# leoTracker.net
KiCad netlist of a schematic drawn in EAGLE
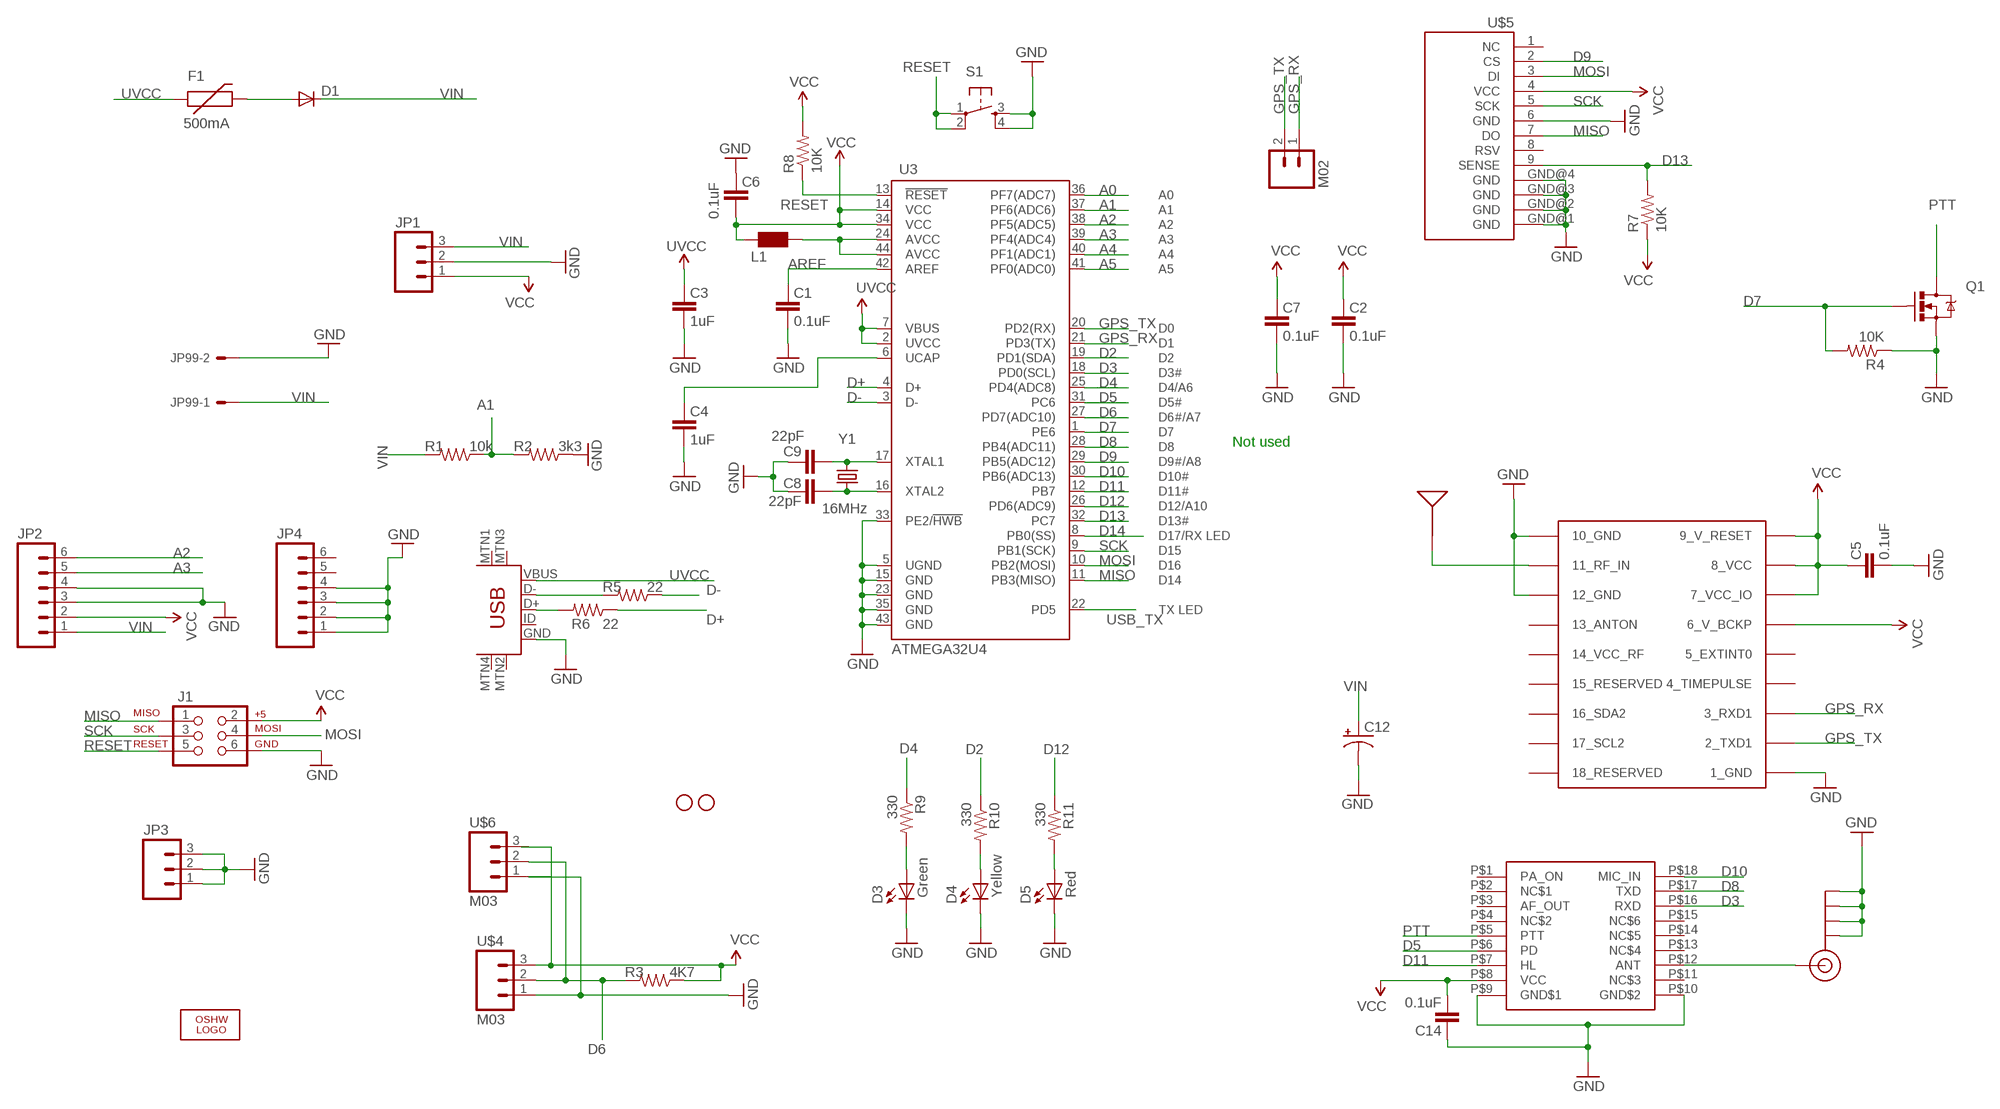
[diagram p0: schematic, sheet 1]

(export (version "E")
  (design (tool "Eeschema 10.0.6"))
  (components
    (comp (ref "C1")
      (value "0.1uF")
      (footprint "eagle-import:0805")
      (libsource (lib "eagle-import") (part "SparkFun-Capacitors_CAP0805"))
    )
    (comp (ref "C2")
      (value "0.1uF")
      (footprint "eagle-import:0402-CAP")
      (libsource (lib "eagle-import") (part "CAP0402-CAP"))
    )
    (comp (ref "C3")
      (value "1uF")
      (footprint "eagle-import:0805")
      (libsource (lib "eagle-import") (part "SparkFun-Capacitors_CAP0805"))
    )
    (comp (ref "C4")
      (value "1uF")
      (footprint "eagle-import:0805")
      (libsource (lib "eagle-import") (part "SparkFun-Capacitors_CAP0805"))
    )
    (comp (ref "C5")
      (value "0.1uF")
      (footprint "eagle-import:0805")
      (libsource (lib "eagle-import") (part "SparkFun-Capacitors_CAP0805"))
    )
    (comp (ref "C6")
      (value "0.1uF")
      (footprint "eagle-import:0805")
      (libsource (lib "eagle-import") (part "SparkFun-Capacitors_CAP0805"))
    )
    (comp (ref "C7")
      (value "0.1uF")
      (footprint "eagle-import:0402-CAP")
      (libsource (lib "eagle-import") (part "CAP0402-CAP"))
    )
    (comp (ref "C8")
      (value "22pF")
      (footprint "eagle-import:0805")
      (libsource (lib "eagle-import") (part "SparkFun-Capacitors_CAP0805"))
    )
    (comp (ref "C9")
      (value "22pF")
      (footprint "eagle-import:0805")
      (libsource (lib "eagle-import") (part "SparkFun-Capacitors_CAP0805"))
    )
    (comp (ref "C12")
      (value "CPOL-US153CLV-0405")
      (footprint "eagle-import:153CLV-0405")
      (libsource (lib "eagle-import") (part "CPOL-US153CLV-0405"))
    )
    (comp (ref "C14")
      (value "0.1uF")
      (footprint "eagle-import:0805")
      (libsource (lib "eagle-import") (part "SparkFun-Capacitors_CAP0805"))
    )
    (comp (ref "D1")
      (value "DIODESOD")
      (footprint "eagle-import:SOD-323")
      (libsource (lib "eagle-import") (part "DIODESOD"))
    )
    (comp (ref "D3")
      (value "Green")
      (footprint "eagle-import:LED-0603")
      (libsource (lib "eagle-import") (part "LED0603"))
    )
    (comp (ref "D4")
      (value "Yellow")
      (footprint "eagle-import:LED-0603")
      (libsource (lib "eagle-import") (part "LED0603"))
    )
    (comp (ref "D5")
      (value "Red")
      (footprint "eagle-import:LED-0603")
      (libsource (lib "eagle-import") (part "LED0603"))
    )
    (comp (ref "F1")
      (value "500mA")
      (footprint "eagle-import:PTC-1206")
      (libsource (lib "eagle-import") (part "PTCSMD"))
    )
    (comp (ref "J$1")
      (value "SMA_EDGE")
      (footprint "eagle-import:SMA-EDGE")
      (libsource (lib "eagle-import") (part "SMA_EDGE"))
    )
    (comp (ref "J1")
      (value "AVR_SPI_PRG_6PTH")
      (footprint "eagle-import:2X3")
      (libsource (lib "eagle-import") (part "AVR_SPI_PRG_6PTH"))
    )
    (comp (ref "JP1")
      (value "M03LOCK")
      (footprint "eagle-import:1X03_LOCK")
      (libsource (lib "eagle-import") (part "M03LOCK"))
    )
    (comp (ref "JP2")
      (value "M06LOCK")
      (footprint "eagle-import:1X06_LOCK")
      (libsource (lib "eagle-import") (part "M06LOCK"))
    )
    (comp (ref "JP3")
      (value "M03LOCK")
      (footprint "eagle-import:1X03_LOCK")
      (libsource (lib "eagle-import") (part "M03LOCK"))
    )
    (comp (ref "JP4")
      (value "M06LOCK")
      (footprint "eagle-import:1X06_LOCK")
      (libsource (lib "eagle-import") (part "M06LOCK"))
    )
    (comp (ref "JP99")
      (value "22-27-2021-02")
      (footprint "eagle-import:6410-02")
      (libsource (lib "eagle-import") (part "22-?-0227-2021"))
    )
    (comp (ref "L1")
      (value "MH2029-300Y")
      (footprint "eagle-import:0805")
      (libsource (lib "eagle-import") (part "WE-CBF_0805"))
    )
    (comp (ref "LOGO1")
      (value "OSHW_LOGO_8MILX0200-NT")
      (footprint "eagle-import:OSHW_8X200_NOTEXT")
      (libsource (lib "eagle-import") (part "OSHW_LOGO_8MILX0200-NT"))
    )
    (comp (ref "Q1")
      (value "MOSFET-NCHANNELSMD")
      (footprint "eagle-import:SOT23-3")
      (libsource (lib "eagle-import") (part "MOSFET-NCHANNELSMD"))
    )
    (comp (ref "R1")
      (value "10k")
      (footprint "eagle-import:0805")
      (libsource (lib "eagle-import") (part "RESISTOR0805-RES"))
    )
    (comp (ref "R2")
      (value "3k3")
      (footprint "eagle-import:0805")
      (libsource (lib "eagle-import") (part "RESISTOR0805-RES"))
    )
    (comp (ref "R3")
      (value "4K7")
      (footprint "eagle-import:0805")
      (libsource (lib "eagle-import") (part "RESISTOR0805-RES"))
    )
    (comp (ref "R4")
      (value "10K")
      (footprint "eagle-import:0805")
      (libsource (lib "eagle-import") (part "RESISTOR0805-RES"))
    )
    (comp (ref "R5")
      (value "22")
      (footprint "eagle-import:0805")
      (libsource (lib "eagle-import") (part "RESISTOR0805-RES"))
    )
    (comp (ref "R6")
      (value "22")
      (footprint "eagle-import:0805")
      (libsource (lib "eagle-import") (part "RESISTOR0805-RES"))
    )
    (comp (ref "R7")
      (value "10K")
      (footprint "eagle-import:0805")
      (libsource (lib "eagle-import") (part "RESISTOR0805-RES"))
    )
    (comp (ref "R8")
      (value "10K")
      (footprint "eagle-import:0805")
      (libsource (lib "eagle-import") (part "RESISTOR0805-RES"))
    )
    (comp (ref "R9")
      (value "330")
      (footprint "eagle-import:0805")
      (libsource (lib "eagle-import") (part "RESISTOR0805-RES"))
    )
    (comp (ref "R10")
      (value "330")
      (footprint "eagle-import:0805")
      (libsource (lib "eagle-import") (part "RESISTOR0805-RES"))
    )
    (comp (ref "R11")
      (value "330")
      (footprint "eagle-import:0805")
      (libsource (lib "eagle-import") (part "RESISTOR0805-RES"))
    )
    (comp (ref "S1")
      (value "TAC_SWITCHSMD")
      (footprint "eagle-import:TACTILE_SWITCH_SMD")
      (libsource (lib "eagle-import") (part "TAC_SWITCHSMD"))
    )
    (comp (ref "STANDOFF1")
      (value "STAND-OFFTIGHT")
      (footprint "eagle-import:STAND-OFF-TIGHT")
      (libsource (lib "eagle-import") (part "STAND-OFFTIGHT"))
    )
    (comp (ref "STANDOFF2")
      (value "STAND-OFFTIGHT")
      (footprint "eagle-import:STAND-OFF-TIGHT")
      (libsource (lib "eagle-import") (part "STAND-OFFTIGHT"))
    )
    (comp (ref "U$1")
      (value "ANTENNA2SMD6")
      (footprint "eagle-import:ANTENNA-CHIP6")
      (libsource (lib "eagle-import") (part "ANTENNA2SMD6"))
    )
    (comp (ref "U$2")
      (value "UBLOX_MAX")
      (footprint "eagle-import:UBLOX_MAX")
      (libsource (lib "eagle-import") (part "UBLOX_MAX"))
    )
    (comp (ref "U$4")
      (value "M03")
      (footprint "eagle-import:M03-JST")
      (libsource (lib "eagle-import") (part "M03"))
    )
    (comp (ref "U$5")
      (value "MICROSD_PI")
      (footprint "eagle-import:MICROSD_PP")
      (libsource (lib "eagle-import") (part "MICROSD_PI"))
    )
    (comp (ref "U$6")
      (value "M03")
      (footprint "eagle-import:M03-JST")
      (libsource (lib "eagle-import") (part "M03"))
    )
    (comp (ref "U$7")
      (value "SA818")
      (footprint "eagle-import:SA818")
      (libsource (lib "eagle-import") (part "SA818"))
    )
    (comp (ref "U$8")
      (value "M02")
      (footprint "eagle-import:M02")
      (libsource (lib "eagle-import") (part "M02"))
    )
    (comp (ref "U3")
      (value "ATMEGA32U4")
      (footprint "eagle-import:SPARKFUN-DIGITALIC_TQFP44")
      (libsource (lib "eagle-import") (part "ATMEGA32U4TQFP"))
    )
    (comp (ref "X1")
      (value "USB-MINIB-5PIN")
      (footprint "eagle-import:USB-MINIB")
      (libsource (lib "eagle-import") (part "USB-MINIB-5PIN"))
    )
    (comp (ref "Y1")
      (value "16MHz")
      (footprint "eagle-import:ABRACON_ABM3_CRYSTAL")
      (libsource (lib "eagle-import") (part "ABRACON_ABM3_CRYSTAL"))
    )
  )
  (nets
    (net (code "1") (name "/A0") (class "Default")
      (node (ref "U3") (pin "36") (pinfunction "PF7(ADC7)_36") (pintype "bidirectional"))
    )
    (net (code "2") (name "/A1") (class "Default")
      (node (ref "R1") (pin "1") (pinfunction "1_1") (pintype "passive"))
      (node (ref "R2") (pin "2") (pinfunction "2_2") (pintype "passive"))
      (node (ref "U3") (pin "37") (pinfunction "PF6(ADC6)_37") (pintype "bidirectional"))
    )
    (net (code "3") (name "/A2") (class "Default")
      (node (ref "JP2") (pin "6") (pinfunction "6_6") (pintype "passive"))
      (node (ref "U3") (pin "38") (pinfunction "PF5(ADC5)_38") (pintype "bidirectional"))
    )
    (net (code "4") (name "/A3") (class "Default")
      (node (ref "JP2") (pin "5") (pinfunction "5_5") (pintype "passive"))
      (node (ref "U3") (pin "39") (pinfunction "PF4(ADC4)_39") (pintype "bidirectional"))
    )
    (net (code "5") (name "/A4") (class "Default")
      (node (ref "U3") (pin "40") (pinfunction "PF1(ADC1)_40") (pintype "bidirectional"))
    )
    (net (code "6") (name "/A5") (class "Default")
      (node (ref "U3") (pin "41") (pinfunction "PF0(ADC0)_41") (pintype "bidirectional"))
    )
    (net (code "7") (name "/AREF") (class "Default")
      (node (ref "C1") (pin "2") (pinfunction "2_2") (pintype "passive"))
      (node (ref "U3") (pin "42") (pinfunction "AREF_42") (pintype "bidirectional"))
    )
    (net (code "8") (name "/D+") (class "Default")
      (node (ref "R6") (pin "1") (pinfunction "1_1") (pintype "passive"))
      (node (ref "U3") (pin "4") (pinfunction "D+_4") (pintype "bidirectional"))
    )
    (net (code "9") (name "/D-") (class "Default")
      (node (ref "R5") (pin "1") (pinfunction "1_1") (pintype "passive"))
      (node (ref "U3") (pin "3") (pinfunction "D-_3") (pintype "bidirectional"))
    )
    (net (code "10") (name "/D2") (class "Default")
      (node (ref "R10") (pin "1") (pinfunction "1_1") (pintype "passive"))
      (node (ref "U3") (pin "19") (pinfunction "PD1(SDA)_19") (pintype "bidirectional"))
    )
    (net (code "11") (name "/D3") (class "Default")
      (node (ref "U$7") (pin "P$16") (pinfunction "RXD_P$16") (pintype "bidirectional"))
      (node (ref "U3") (pin "18") (pinfunction "PD0(SCL)_18") (pintype "bidirectional"))
    )
    (net (code "12") (name "/D4") (class "Default")
      (node (ref "R9") (pin "1") (pinfunction "1_1") (pintype "passive"))
      (node (ref "U3") (pin "25") (pinfunction "PD4(ADC8)_25") (pintype "bidirectional"))
    )
    (net (code "13") (name "/D5") (class "Default")
      (node (ref "U$7") (pin "P$6") (pinfunction "PD_P$6") (pintype "bidirectional"))
      (node (ref "U3") (pin "31") (pinfunction "PC6_31") (pintype "bidirectional"))
    )
    (net (code "14") (name "/D6") (class "Default")
      (node (ref "R3") (pin "2") (pinfunction "2_2") (pintype "passive"))
      (node (ref "U$4") (pin "2") (pinfunction "2_2") (pintype "passive"))
      (node (ref "U$6") (pin "2") (pinfunction "2_2") (pintype "passive"))
      (node (ref "U3") (pin "27") (pinfunction "PD7(ADC10)_27") (pintype "bidirectional"))
    )
    (net (code "15") (name "/D7") (class "Default")
      (node (ref "Q1") (pin "1") (pinfunction "G_1") (pintype "passive"))
      (node (ref "R4") (pin "2") (pinfunction "2_2") (pintype "passive"))
      (node (ref "U3") (pin "1") (pinfunction "PE6_1") (pintype "bidirectional"))
    )
    (net (code "16") (name "/D8") (class "Default")
      (node (ref "U$7") (pin "P$17") (pinfunction "TXD_P$17") (pintype "bidirectional"))
      (node (ref "U3") (pin "28") (pinfunction "PB4(ADC11)_28") (pintype "bidirectional"))
    )
    (net (code "17") (name "/D9") (class "Default")
      (node (ref "U$5") (pin "2") (pinfunction "CS_2") (pintype "bidirectional"))
      (node (ref "U3") (pin "29") (pinfunction "PB5(ADC12)_29") (pintype "bidirectional"))
    )
    (net (code "18") (name "/D10") (class "Default")
      (node (ref "U$7") (pin "P$18") (pinfunction "MIC_IN_P$18") (pintype "bidirectional"))
      (node (ref "U3") (pin "30") (pinfunction "PB6(ADC13)_30") (pintype "bidirectional"))
    )
    (net (code "19") (name "/D11") (class "Default")
      (node (ref "U$7") (pin "P$7") (pinfunction "HL_P$7") (pintype "bidirectional"))
      (node (ref "U3") (pin "12") (pinfunction "PB7_12") (pintype "bidirectional"))
    )
    (net (code "20") (name "/D12") (class "Default")
      (node (ref "R11") (pin "1") (pinfunction "1_1") (pintype "passive"))
      (node (ref "U3") (pin "26") (pinfunction "PD6(ADC9)_26") (pintype "bidirectional"))
    )
    (net (code "21") (name "/D13") (class "Default")
      (node (ref "R7") (pin "2") (pinfunction "2_2") (pintype "passive"))
      (node (ref "U$5") (pin "9") (pinfunction "SENSE_9") (pintype "bidirectional"))
      (node (ref "U3") (pin "32") (pinfunction "PC7_32") (pintype "bidirectional"))
    )
    (net (code "22") (name "/D14") (class "Default")
      (node (ref "U3") (pin "8") (pinfunction "PB0(SS)_8") (pintype "bidirectional"))
    )
    (net (code "23") (name "/GPS_RX") (class "Default")
      (node (ref "U$2") (pin "3_RXD1") (pinfunction "3_RXD1_3_RXD1") (pintype "bidirectional"))
      (node (ref "U$8") (pin "1") (pinfunction "1_1") (pintype "passive"))
      (node (ref "U3") (pin "21") (pinfunction "PD3(TX)_21") (pintype "bidirectional"))
    )
    (net (code "24") (name "/GPS_TX") (class "Default")
      (node (ref "U$2") (pin "2_TXD1") (pinfunction "2_TXD1_2_TXD1") (pintype "bidirectional"))
      (node (ref "U$8") (pin "2") (pinfunction "2_2") (pintype "passive"))
      (node (ref "U3") (pin "20") (pinfunction "PD2(RX)_20") (pintype "bidirectional"))
    )
    (net (code "25") (name "/MISO") (class "Default")
      (node (ref "J1") (pin "1") (pinfunction "1_1") (pintype "passive"))
      (node (ref "U$5") (pin "7") (pinfunction "DO_7") (pintype "bidirectional"))
      (node (ref "U3") (pin "11") (pinfunction "PB3(MISO)_11") (pintype "bidirectional"))
    )
    (net (code "26") (name "/MOSI") (class "Default")
      (node (ref "J1") (pin "4") (pinfunction "4_4") (pintype "passive"))
      (node (ref "U$5") (pin "3") (pinfunction "DI_3") (pintype "bidirectional"))
      (node (ref "U3") (pin "10") (pinfunction "PB2(MOSI)_10") (pintype "bidirectional"))
    )
    (net (code "27") (name "/PTT") (class "Default")
      (node (ref "Q1") (pin "3") (pinfunction "D_3") (pintype "passive"))
      (node (ref "U$7") (pin "P$5") (pinfunction "PTT_P$5") (pintype "bidirectional"))
    )
    (net (code "28") (name "/RESET") (class "Default")
      (node (ref "J1") (pin "5") (pinfunction "5_5") (pintype "passive"))
      (node (ref "R8") (pin "1") (pinfunction "1_1") (pintype "passive"))
      (node (ref "S1") (pin "1") (pinfunction "1_1") (pintype "passive"))
      (node (ref "S1") (pin "2") (pinfunction "2_2") (pintype "passive"))
      (node (ref "U3") (pin "13") (pinfunction "~{RESET}_13") (pintype "bidirectional"))
    )
    (net (code "29") (name "/SCK") (class "Default")
      (node (ref "J1") (pin "3") (pinfunction "3_3") (pintype "passive"))
      (node (ref "U$5") (pin "5") (pinfunction "SCK_5") (pintype "bidirectional"))
      (node (ref "U3") (pin "9") (pinfunction "PB1(SCK)_9") (pintype "bidirectional"))
    )
    (net (code "30") (name "/USB_TX") (class "Default")
      (node (ref "U3") (pin "22") (pinfunction "PD5_22") (pintype "bidirectional"))
    )
    (net (code "31") (name "/VIN") (class "Default")
      (node (ref "C12") (pin "+") (pinfunction "+_+") (pintype "passive"))
      (node (ref "D1") (pin "1") (pinfunction "C_1") (pintype "passive"))
      (node (ref "JP1") (pin "3") (pinfunction "3_3") (pintype "passive"))
      (node (ref "JP2") (pin "1") (pinfunction "1_1") (pintype "passive"))
      (node (ref "JP99") (pin "1") (pinfunction "S_1") (pintype "passive"))
      (node (ref "R1") (pin "2") (pinfunction "2_2") (pintype "passive"))
    )
    (net (code "32") (name "GND") (class "Default")
      (node (ref "C1") (pin "1") (pinfunction "1_1") (pintype "passive"))
      (node (ref "C12") (pin "-") (pinfunction "-_-") (pintype "passive"))
      (node (ref "C14") (pin "2") (pinfunction "2_2") (pintype "passive"))
      (node (ref "C2") (pin "1") (pinfunction "1_1") (pintype "passive"))
      (node (ref "C3") (pin "1") (pinfunction "1_1") (pintype "passive"))
      (node (ref "C4") (pin "1") (pinfunction "1_1") (pintype "passive"))
      (node (ref "C5") (pin "1") (pinfunction "1_1") (pintype "passive"))
      (node (ref "C6") (pin "2") (pinfunction "2_2") (pintype "passive"))
      (node (ref "C7") (pin "1") (pinfunction "1_1") (pintype "passive"))
      (node (ref "C8") (pin "2") (pinfunction "2_2") (pintype "passive"))
      (node (ref "C9") (pin "2") (pinfunction "2_2") (pintype "passive"))
      (node (ref "D3") (pin "C") (pinfunction "C_C") (pintype "passive"))
      (node (ref "D4") (pin "C") (pinfunction "C_C") (pintype "passive"))
      (node (ref "D5") (pin "C") (pinfunction "C_C") (pintype "passive"))
      (node (ref "J$1") (pin "GND@0") (pinfunction "GND_GND@0") (pintype "bidirectional"))
      (node (ref "J$1") (pin "GND@1") (pinfunction "GND_GND@1") (pintype "bidirectional"))
      (node (ref "J$1") (pin "GND@2") (pinfunction "GND_GND@2") (pintype "bidirectional"))
      (node (ref "J$1") (pin "GND@3") (pinfunction "GND_GND@3") (pintype "bidirectional"))
      (node (ref "J1") (pin "6") (pinfunction "6_6") (pintype "passive"))
      (node (ref "JP1") (pin "2") (pinfunction "2_2") (pintype "passive"))
      (node (ref "JP2") (pin "3") (pinfunction "3_3") (pintype "passive"))
      (node (ref "JP2") (pin "4") (pinfunction "4_4") (pintype "passive"))
      (node (ref "JP3") (pin "1") (pinfunction "1_1") (pintype "passive"))
      (node (ref "JP3") (pin "2") (pinfunction "2_2") (pintype "passive"))
      (node (ref "JP3") (pin "3") (pinfunction "3_3") (pintype "passive"))
      (node (ref "JP4") (pin "1") (pinfunction "1_1") (pintype "passive"))
      (node (ref "JP4") (pin "2") (pinfunction "2_2") (pintype "passive"))
      (node (ref "JP4") (pin "3") (pinfunction "3_3") (pintype "passive"))
      (node (ref "JP4") (pin "4") (pinfunction "4_4") (pintype "passive"))
      (node (ref "JP99") (pin "2") (pinfunction "S_2") (pintype "passive"))
      (node (ref "Q1") (pin "2") (pinfunction "S_2") (pintype "passive"))
      (node (ref "R2") (pin "1") (pinfunction "1_1") (pintype "passive"))
      (node (ref "R4") (pin "1") (pinfunction "1_1") (pintype "passive"))
      (node (ref "S1") (pin "3") (pinfunction "3_3") (pintype "passive"))
      (node (ref "S1") (pin "4") (pinfunction "4_4") (pintype "passive"))
      (node (ref "U$2") (pin "10_GND") (pinfunction "10_GND_10_GND") (pintype "power_in"))
      (node (ref "U$2") (pin "12_GND") (pinfunction "12_GND_12_GND") (pintype "power_in"))
      (node (ref "U$2") (pin "1_GND") (pinfunction "1_GND_1_GND") (pintype "power_in"))
      (node (ref "U$4") (pin "1") (pinfunction "1_1") (pintype "passive"))
      (node (ref "U$5") (pin "6") (pinfunction "GND_6") (pintype "bidirectional"))
      (node (ref "U$5") (pin "GND@1") (pinfunction "GND_GND@1") (pintype "bidirectional"))
      (node (ref "U$5") (pin "GND@2") (pinfunction "GND_GND@2") (pintype "bidirectional"))
      (node (ref "U$5") (pin "GND@3") (pinfunction "GND_GND@3") (pintype "bidirectional"))
      (node (ref "U$5") (pin "GND@4") (pinfunction "GND_GND@4") (pintype "bidirectional"))
      (node (ref "U$6") (pin "1") (pinfunction "1_1") (pintype "passive"))
      (node (ref "U$7") (pin "P$10") (pinfunction "GND$2_P$10") (pintype "bidirectional"))
      (node (ref "U$7") (pin "P$9") (pinfunction "GND$1_P$9") (pintype "bidirectional"))
      (node (ref "U3") (pin "15") (pinfunction "GND_15") (pintype "bidirectional"))
      (node (ref "U3") (pin "23") (pinfunction "GND_23") (pintype "bidirectional"))
      (node (ref "U3") (pin "33") (pinfunction "PE2/~{HWB}_33") (pintype "bidirectional"))
      (node (ref "U3") (pin "35") (pinfunction "GND_35") (pintype "bidirectional"))
      (node (ref "U3") (pin "43") (pinfunction "GND_43") (pintype "bidirectional"))
      (node (ref "U3") (pin "5") (pinfunction "UGND_5") (pintype "bidirectional"))
      (node (ref "X1") (pin "GND") (pinfunction "GND_GND") (pintype "bidirectional"))
    )
    (net (code "33") (name "Net-(D1-A)") (class "Default")
      (node (ref "D1") (pin "2") (pinfunction "A_2") (pintype "passive"))
      (node (ref "F1") (pin "2") (pinfunction "2_2") (pintype "bidirectional"))
    )
    (net (code "34") (name "Net-(D3-PadA)") (class "Default")
      (node (ref "D3") (pin "A") (pinfunction "A_A") (pintype "passive"))
      (node (ref "R9") (pin "2") (pinfunction "2_2") (pintype "passive"))
    )
    (net (code "35") (name "Net-(D4-PadA)") (class "Default")
      (node (ref "D4") (pin "A") (pinfunction "A_A") (pintype "passive"))
      (node (ref "R10") (pin "2") (pinfunction "2_2") (pintype "passive"))
    )
    (net (code "36") (name "Net-(D5-PadA)") (class "Default")
      (node (ref "D5") (pin "A") (pinfunction "A_A") (pintype "passive"))
      (node (ref "R11") (pin "2") (pinfunction "2_2") (pintype "passive"))
    )
    (net (code "37") (name "Net-(J$1-SIGNAL)") (class "Default")
      (node (ref "J$1") (pin "SIG") (pinfunction "SIGNAL_SIG") (pintype "bidirectional"))
      (node (ref "U$7") (pin "P$12") (pinfunction "ANT_P$12") (pintype "bidirectional"))
    )
    (net (code "38") (name "Net-(L1-Pad2)") (class "Default")
      (node (ref "L1") (pin "2") (pinfunction "2_2") (pintype "passive"))
      (node (ref "U3") (pin "24") (pinfunction "AVCC_24") (pintype "bidirectional"))
      (node (ref "U3") (pin "44") (pinfunction "AVCC_44") (pintype "bidirectional"))
    )
    (net (code "39") (name "Net-(R5-Pad2)") (class "Default")
      (node (ref "R5") (pin "2") (pinfunction "2_2") (pintype "passive"))
      (node (ref "X1") (pin "D-") (pinfunction "D-_D-") (pintype "bidirectional"))
    )
    (net (code "40") (name "Net-(R6-Pad2)") (class "Default")
      (node (ref "R6") (pin "2") (pinfunction "2_2") (pintype "passive"))
      (node (ref "X1") (pin "D+") (pinfunction "D+_D+") (pintype "bidirectional"))
    )
    (net (code "41") (name "Net-(U$1-SIGNAL)") (class "Default")
      (node (ref "U$1") (pin "1") (pinfunction "SIGNAL_1") (pintype "bidirectional"))
      (node (ref "U$2") (pin "11_RF_IN") (pinfunction "11_RF_IN_11_RF_IN") (pintype "bidirectional"))
    )
    (net (code "42") (name "Net-(U3-UCAP)") (class "Default")
      (node (ref "C4") (pin "2") (pinfunction "2_2") (pintype "passive"))
      (node (ref "U3") (pin "6") (pinfunction "UCAP_6") (pintype "bidirectional"))
    )
    (net (code "43") (name "Net-(U3-XTAL1)") (class "Default")
      (node (ref "C9") (pin "1") (pinfunction "1_1") (pintype "passive"))
      (node (ref "U3") (pin "17") (pinfunction "XTAL1_17") (pintype "bidirectional"))
      (node (ref "Y1") (pin "P$2") (pinfunction "2_P$2") (pintype "passive"))
    )
    (net (code "44") (name "Net-(U3-XTAL2)") (class "Default")
      (node (ref "C8") (pin "1") (pinfunction "1_1") (pintype "passive"))
      (node (ref "U3") (pin "16") (pinfunction "XTAL2_16") (pintype "bidirectional"))
      (node (ref "Y1") (pin "P$1") (pinfunction "1_P$1") (pintype "passive"))
    )
    (net (code "45") (name "UVCC") (class "Default")
      (node (ref "C3") (pin "2") (pinfunction "2_2") (pintype "passive"))
      (node (ref "F1") (pin "1") (pinfunction "1_1") (pintype "bidirectional"))
      (node (ref "U3") (pin "2") (pinfunction "UVCC_2") (pintype "bidirectional"))
      (node (ref "U3") (pin "7") (pinfunction "VBUS_7") (pintype "bidirectional"))
      (node (ref "X1") (pin "VBUS") (pinfunction "VBUS_VBUS") (pintype "bidirectional"))
    )
    (net (code "46") (name "VCC") (class "Default")
      (node (ref "C14") (pin "1") (pinfunction "1_1") (pintype "passive"))
      (node (ref "C2") (pin "2") (pinfunction "2_2") (pintype "passive"))
      (node (ref "C5") (pin "2") (pinfunction "2_2") (pintype "passive"))
      (node (ref "C6") (pin "1") (pinfunction "1_1") (pintype "passive"))
      (node (ref "C7") (pin "2") (pinfunction "2_2") (pintype "passive"))
      (node (ref "J1") (pin "2") (pinfunction "2_2") (pintype "passive"))
      (node (ref "JP1") (pin "1") (pinfunction "1_1") (pintype "passive"))
      (node (ref "JP2") (pin "2") (pinfunction "2_2") (pintype "passive"))
      (node (ref "L1") (pin "1") (pinfunction "1_1") (pintype "passive"))
      (node (ref "R3") (pin "1") (pinfunction "1_1") (pintype "passive"))
      (node (ref "R7") (pin "1") (pinfunction "1_1") (pintype "passive"))
      (node (ref "R8") (pin "2") (pinfunction "2_2") (pintype "passive"))
      (node (ref "U$2") (pin "6_V_BCKP") (pinfunction "6_V_BCKP_6_V_BCKP") (pintype "bidirectional"))
      (node (ref "U$2") (pin "7_VCC_IO") (pinfunction "7_VCC_IO_7_VCC_IO") (pintype "power_in"))
      (node (ref "U$2") (pin "8_VCC") (pinfunction "8_VCC_8_VCC") (pintype "power_in"))
      (node (ref "U$2") (pin "9_V_RESET") (pinfunction "9_V_RESET_9_V_RESET") (pintype "power_in"))
      (node (ref "U$4") (pin "3") (pinfunction "3_3") (pintype "passive"))
      (node (ref "U$5") (pin "4") (pinfunction "VCC_4") (pintype "bidirectional"))
      (node (ref "U$6") (pin "3") (pinfunction "3_3") (pintype "passive"))
      (node (ref "U$7") (pin "P$8") (pinfunction "VCC_P$8") (pintype "bidirectional"))
      (node (ref "U3") (pin "14") (pinfunction "VCC_14") (pintype "bidirectional"))
      (node (ref "U3") (pin "34") (pinfunction "VCC_34") (pintype "bidirectional"))
    )
    (net (code "47") (name "unconnected-(JP4-Pad5)") (class "Default")
      (node (ref "JP4") (pin "5") (pinfunction "5_5") (pintype "passive"))
    )
    (net (code "48") (name "unconnected-(JP4-Pad6)") (class "Default")
      (node (ref "JP4") (pin "6") (pinfunction "6_6") (pintype "passive"))
    )
    (net (code "49") (name "unconnected-(U$2-Pad4_TIMEPULSE)") (class "Default")
      (node (ref "U$2") (pin "4_TIMEPULSE") (pinfunction "4_TIMEPULSE_4_TIMEPULSE") (pintype "bidirectional"))
    )
    (net (code "50") (name "unconnected-(U$2-Pad5_EXTINT0)") (class "Default")
      (node (ref "U$2") (pin "5_EXTINT0") (pinfunction "5_EXTINT0_5_EXTINT0") (pintype "bidirectional"))
    )
    (net (code "51") (name "unconnected-(U$2-Pad13_ANTON)") (class "Default")
      (node (ref "U$2") (pin "13_ANTON") (pinfunction "13_ANTON_13_ANTON") (pintype "bidirectional"))
    )
    (net (code "52") (name "unconnected-(U$2-Pad14_VCC_RF)") (class "Default")
      (node (ref "U$2") (pin "14_VCC_RF") (pinfunction "14_VCC_RF_14_VCC_RF") (pintype "bidirectional"))
    )
    (net (code "53") (name "unconnected-(U$2-Pad15_RESERVED)") (class "Default")
      (node (ref "U$2") (pin "15_RESERVED") (pinfunction "15_RESERVED_15_RESERVED") (pintype "bidirectional"))
    )
    (net (code "54") (name "unconnected-(U$2-Pad16_SDA2)") (class "Default")
      (node (ref "U$2") (pin "16_SDA2") (pinfunction "16_SDA2_16_SDA2") (pintype "bidirectional"))
    )
    (net (code "55") (name "unconnected-(U$2-Pad17_SCL2)") (class "Default")
      (node (ref "U$2") (pin "17_SCL2") (pinfunction "17_SCL2_17_SCL2") (pintype "bidirectional"))
    )
    (net (code "56") (name "unconnected-(U$2-Pad18_RESERVED)") (class "Default")
      (node (ref "U$2") (pin "18_RESERVED") (pinfunction "18_RESERVED_18_RESERVED") (pintype "bidirectional"))
    )
    (net (code "57") (name "unconnected-(U$5-NC-Pad1)") (class "Default")
      (node (ref "U$5") (pin "1") (pinfunction "NC_1") (pintype "bidirectional"))
    )
    (net (code "58") (name "unconnected-(U$5-RSV-Pad8)") (class "Default")
      (node (ref "U$5") (pin "8") (pinfunction "RSV_8") (pintype "bidirectional"))
    )
    (net (code "59") (name "unconnected-(U$7-AF_OUT-PadP$3)") (class "Default")
      (node (ref "U$7") (pin "P$3") (pinfunction "AF_OUT_P$3") (pintype "bidirectional"))
    )
    (net (code "60") (name "unconnected-(U$7-NC$1-PadP$2)") (class "Default")
      (node (ref "U$7") (pin "P$2") (pinfunction "NC$1_P$2") (pintype "bidirectional"))
    )
    (net (code "61") (name "unconnected-(U$7-NC$2-PadP$4)") (class "Default")
      (node (ref "U$7") (pin "P$4") (pinfunction "NC$2_P$4") (pintype "bidirectional"))
    )
    (net (code "62") (name "unconnected-(U$7-NC$3-PadP$11)") (class "Default")
      (node (ref "U$7") (pin "P$11") (pinfunction "NC$3_P$11") (pintype "bidirectional"))
    )
    (net (code "63") (name "unconnected-(U$7-NC$4-PadP$13)") (class "Default")
      (node (ref "U$7") (pin "P$13") (pinfunction "NC$4_P$13") (pintype "bidirectional"))
    )
    (net (code "64") (name "unconnected-(U$7-NC$5-PadP$14)") (class "Default")
      (node (ref "U$7") (pin "P$14") (pinfunction "NC$5_P$14") (pintype "bidirectional"))
    )
    (net (code "65") (name "unconnected-(U$7-NC$6-PadP$15)") (class "Default")
      (node (ref "U$7") (pin "P$15") (pinfunction "NC$6_P$15") (pintype "bidirectional"))
    )
    (net (code "66") (name "unconnected-(U$7-PA_ON-PadP$1)") (class "Default")
      (node (ref "U$7") (pin "P$1") (pinfunction "PA_ON_P$1") (pintype "bidirectional"))
    )
    (net (code "67") (name "unconnected-(X1-MTN1-PadMTN3)") (class "Default")
      (node (ref "X1") (pin "MTN3") (pinfunction "MTN1_MTN3") (pintype "bidirectional"))
    )
    (net (code "68") (name "unconnected-(X1-MTN2-PadMTN1)") (class "Default")
      (node (ref "X1") (pin "MTN1") (pinfunction "MTN2_MTN1") (pintype "bidirectional"))
    )
    (net (code "69") (name "unconnected-(X1-MTN3-PadMTN2)") (class "Default")
      (node (ref "X1") (pin "MTN2") (pinfunction "MTN3_MTN2") (pintype "bidirectional"))
    )
    (net (code "70") (name "unconnected-(X1-PadID)") (class "Default")
      (node (ref "X1") (pin "ID") (pinfunction "ID_ID") (pintype "bidirectional"))
    )
    (net (code "71") (name "unconnected-(X1-PadMTN4)") (class "Default")
      (node (ref "X1") (pin "MTN4") (pinfunction "MTN4_MTN4") (pintype "bidirectional"))
    )
  )
)
